# Microphone2.net
KiCad netlist of a schematic drawn in Altium Designer
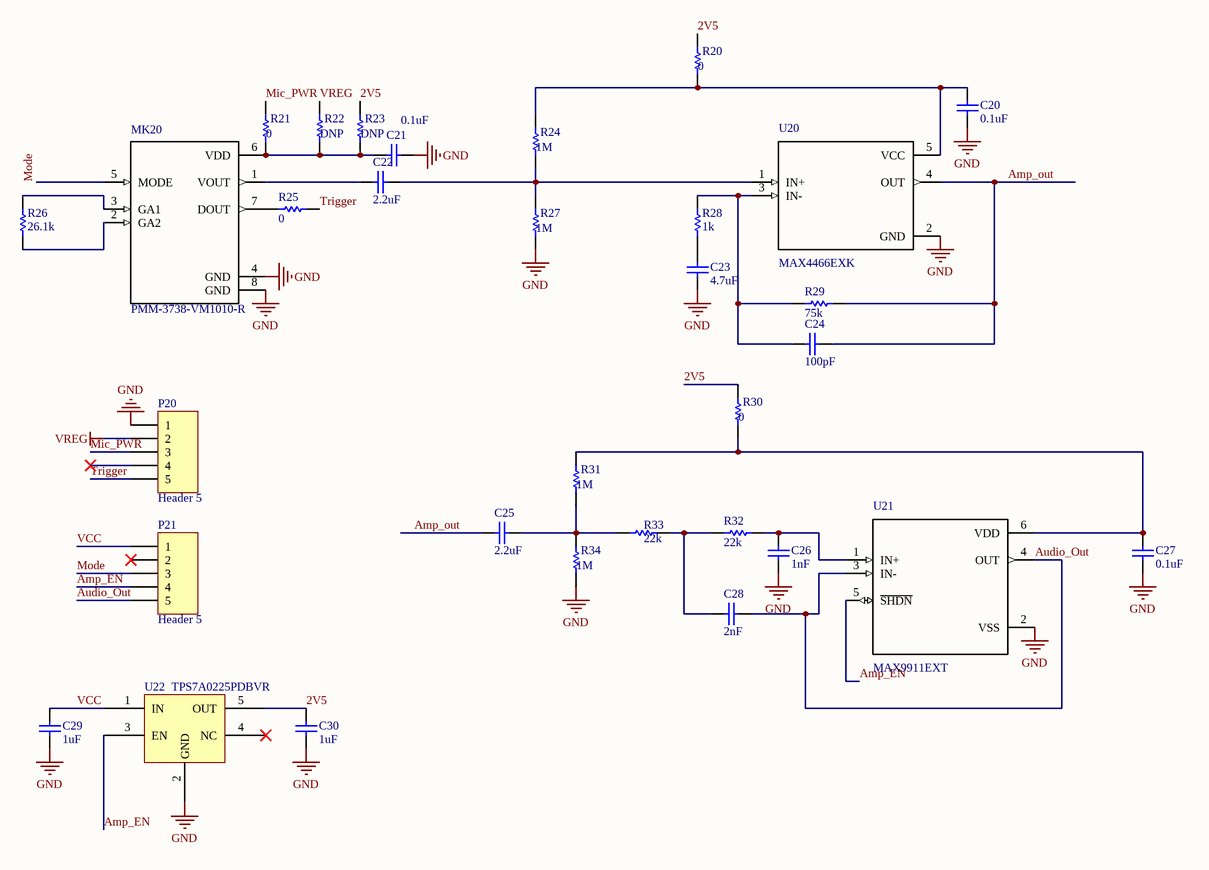
[diagram p0: Microphone2.SchDoc]

(export (version "E")
  (design (tool "Eeschema 10.0.6"))
  (components
    (comp (ref "C20")
      (value "0.1uF")
      (footprint "0402")
      (description "Ceramic Capacitor (Surface Mount)")
      (fields
        (field (name "DIGI-KEY PART NUMBER") "490-4759-1-ND")
        (field (name "MANUFACTURER") "Murata Electronics North America")
      )
      (libsource (lib "WISP_AD10") (part "Cap"))
    )
    (comp (ref "C21")
      (value "0.1uF")
      (footprint "0402")
      (description "Ceramic Capacitor (Surface Mount)")
      (fields
        (field (name "DIGI-KEY PART NUMBER") "490-4759-1-ND")
        (field (name "MANUFACTURER") "Murata Electronics North America")
      )
      (libsource (lib "WISP_AD10") (part "Cap"))
    )
    (comp (ref "C22")
      (value "2.2uF")
      (footprint "0402")
      (description "Ceramic Capacitor (Surface Mount)")
      (fields (field (name "DIGI-KEY PART NUMBER") "311-0.0JRCT-ND") (field (name "MANUFACTURER") "Yageo"))
      (libsource (lib "WISP_AD10") (part "Cap"))
    )
    (comp (ref "C23")
      (value "4.7uF")
      (footprint "0402")
      (description "Ceramic Capacitor (Surface Mount)")
      (fields
        (field (name "DIGI-KEY PART NUMBER") "490-14306-1-ND")
        (field (name "MANUFACTURER") "Murata Electronics")
      )
      (libsource (lib "WISP_AD10") (part "Cap"))
    )
    (comp (ref "C24")
      (value "100pF")
      (footprint "0402")
      (description "Ceramic Capacitor (Surface Mount)")
      (fields (field (name "DIGI-KEY PART NUMBER") "311-1024-1-ND") (field (name "MANUFACTURER") "Yageo"))
      (libsource (lib "WISP_AD10") (part "Cap"))
    )
    (comp (ref "C25")
      (value "2.2uF")
      (footprint "0402")
      (description "Ceramic Capacitor (Surface Mount)")
      (fields (field (name "DIGI-KEY PART NUMBER") "311-0.0JRCT-ND") (field (name "MANUFACTURER") "Yageo"))
      (libsource (lib "WISP_AD10") (part "Cap"))
    )
    (comp (ref "C26")
      (value "1nF")
      (footprint "0402")
      (description "Ceramic Capacitor (Surface Mount)")
      (fields
        (field (name "DIGI-KEY PART NUMBER") "490-4761-1-ND")
        (field (name "MANUFACTURER") "Murata Electronics")
      )
      (libsource (lib "WISP_AD10") (part "Cap"))
    )
    (comp (ref "C27")
      (value "0.1uF")
      (footprint "0402")
      (description "Ceramic Capacitor (Surface Mount)")
      (fields
        (field (name "DIGI-KEY PART NUMBER") "490-4759-1-ND")
        (field (name "MANUFACTURER") "Murata Electronics North America")
      )
      (libsource (lib "WISP_AD10") (part "Cap"))
    )
    (comp (ref "C28")
      (value "2nF")
      (footprint "0402")
      (description "Ceramic Capacitor (Surface Mount)")
      (fields
        (field (name "DIGI-KEY PART NUMBER") "478-10122-1-ND")
        (field (name "MANUFACTURER") "AVX Corporation")
      )
      (libsource (lib "WISP_AD10") (part "Cap"))
    )
    (comp (ref "C29")
      (value "1uF")
      (footprint "0402")
      (description "Ceramic Capacitor (Surface Mount)")
      (fields (field (name "DIGI-KEY PART NUMBER") "311-0.0JRCT-ND") (field (name "MANUFACTURER") "Yageo"))
      (libsource (lib "WISP_AD10") (part "Cap"))
    )
    (comp (ref "C30")
      (value "1uF")
      (footprint "0402")
      (description "Ceramic Capacitor (Surface Mount)")
      (fields (field (name "DIGI-KEY PART NUMBER") "311-0.0JRCT-ND") (field (name "MANUFACTURER") "Yageo"))
      (libsource (lib "WISP_AD10") (part "Cap"))
    )
    (comp (ref "MK20")
      (value "PMM-3738-VM1010-R")
      (footprint "MIC_PMM-3738-VM1010-R")
      (description "MEMS Microphone Omni-Directional 700 Ohm -38dBV 1.8V Rectangular Solder Pad T/R")
      (fields
        (field (name "MANUFACTURER PART NUMBER") "VM1010")
        (field (name "MANUFACTURER") "Vesper Technologies Inc.")
      )
      (libsource (lib "BLE") (part "PMM-3738-VM1010-R"))
    )
    (comp (ref "P20")
      (value "Header 5")
      (footprint "HDR1X5")
      (description "Header, 5-Pin")
      (fields (field (name "PUBLISHER") "Altium Limited"))
      (libsource (lib "Miscellaneous Connectors") (part "Header 5"))
    )
    (comp (ref "P21")
      (value "Header 5")
      (footprint "HDR1X5")
      (description "Header, 5-Pin")
      (fields (field (name "PUBLISHER") "Altium Limited"))
      (libsource (lib "Miscellaneous Connectors") (part "Header 5"))
    )
    (comp (ref "R20")
      (value "0")
      (footprint "0402")
      (description "Chip Resistor (Surface Mount)")
      (fields
        (field (name "MANUFACTURER") "Yageo")
        (field (name "MANUFACTURER PART NUMBER") "RC0402FR-071ML")
      )
      (libsource (lib "WISP_AD10") (part "Res"))
    )
    (comp (ref "R21")
      (value "0")
      (footprint "0402")
      (description "Chip Resistor (Surface Mount)")
      (fields
        (field (name "MANUFACTURER") "Yageo")
        (field (name "MANUFACTURER PART NUMBER") "RC0402FR-071ML")
      )
      (libsource (lib "WISP_AD10") (part "Res"))
    )
    (comp (ref "R22")
      (value "DNP")
      (footprint "0402")
      (description "Chip Resistor (Surface Mount)")
      (fields
        (field (name "MANUFACTURER") "Yageo")
        (field (name "MANUFACTURER PART NUMBER") "RC0402FR-071ML")
      )
      (libsource (lib "WISP_AD10") (part "Res"))
    )
    (comp (ref "R23")
      (value "DNP")
      (footprint "0402")
      (description "Chip Resistor (Surface Mount)")
      (fields
        (field (name "MANUFACTURER") "Yageo")
        (field (name "MANUFACTURER PART NUMBER") "RC0402FR-071ML")
      )
      (libsource (lib "WISP_AD10") (part "Res"))
    )
    (comp (ref "R24")
      (value "1M")
      (footprint "0402")
      (description "Chip Resistor (Surface Mount)")
      (fields
        (field (name "MANUFACTURER") "Yageo")
        (field (name "MANUFACTURER PART NUMBER") "RC0402FR-071ML")
      )
      (libsource (lib "WISP_AD10") (part "Res"))
    )
    (comp (ref "R25")
      (value "0")
      (footprint "0402")
      (description "Chip Resistor (Surface Mount)")
      (fields
        (field (name "MANUFACTURER") "Yageo")
        (field (name "MANUFACTURER PART NUMBER") "RC0402JR-070RL")
      )
      (libsource (lib "WISP_AD10") (part "Res"))
    )
    (comp (ref "R26")
      (value "26.1k")
      (footprint "0402")
      (description "Chip Resistor (Surface Mount)")
      (fields
        (field (name "MANUFACTURER") "Yageo")
        (field (name "MANUFACTURER PART NUMBER") "RC0402FR-0726K1L")
      )
      (libsource (lib "WISP_AD10") (part "Res"))
    )
    (comp (ref "R27")
      (value "1M")
      (footprint "0402")
      (description "Chip Resistor (Surface Mount)")
      (fields
        (field (name "MANUFACTURER") "Yageo")
        (field (name "MANUFACTURER PART NUMBER") "RC0402FR-071ML")
      )
      (libsource (lib "WISP_AD10") (part "Res"))
    )
    (comp (ref "R28")
      (value "1k")
      (footprint "0402")
      (description "Chip Resistor (Surface Mount)")
      (fields
        (field (name "MANUFACTURER") "Yageo")
        (field (name "MANUFACTURER PART NUMBER") "RC0402FR-071KL")
      )
      (libsource (lib "WISP_AD10") (part "Res"))
    )
    (comp (ref "R29")
      (value "75k")
      (footprint "0402")
      (description "Chip Resistor (Surface Mount)")
      (fields
        (field (name "MANUFACTURER") "Yageo")
        (field (name "MANUFACTURER PART NUMBER") "RC0402FR-0775KL")
      )
      (libsource (lib "WISP_AD10") (part "Res"))
    )
    (comp (ref "R30")
      (value "0")
      (footprint "0402")
      (description "Chip Resistor (Surface Mount)")
      (fields
        (field (name "MANUFACTURER") "Yageo")
        (field (name "MANUFACTURER PART NUMBER") "RC0402FR-071ML")
      )
      (libsource (lib "WISP_AD10") (part "Res"))
    )
    (comp (ref "R31")
      (value "1M")
      (footprint "0402")
      (description "Chip Resistor (Surface Mount)")
      (fields
        (field (name "MANUFACTURER") "Yageo")
        (field (name "MANUFACTURER PART NUMBER") "RC0402FR-071ML")
      )
      (libsource (lib "WISP_AD10") (part "Res"))
    )
    (comp (ref "R32")
      (value "22k")
      (footprint "0402")
      (description "Chip Resistor (Surface Mount)")
      (fields
        (field (name "MANUFACTURER") "Yageo")
        (field (name "MANUFACTURER PART NUMBER") "RT0402BRD0722KL")
      )
      (libsource (lib "WISP_AD10") (part "Res"))
    )
    (comp (ref "R33")
      (value "22k")
      (footprint "0402")
      (description "Chip Resistor (Surface Mount)")
      (fields
        (field (name "MANUFACTURER") "Yageo")
        (field (name "MANUFACTURER PART NUMBER") "RT0402BRD0722KL")
      )
      (libsource (lib "WISP_AD10") (part "Res"))
    )
    (comp (ref "R34")
      (value "1M")
      (footprint "0402")
      (description "Chip Resistor (Surface Mount)")
      (fields
        (field (name "MANUFACTURER") "Yageo")
        (field (name "MANUFACTURER PART NUMBER") "RC0402FR-071ML")
      )
      (libsource (lib "WISP_AD10") (part "Res"))
    )
    (comp (ref "U20")
      (value "MAX4466EXK")
      (footprint "SOT65P210X110-5N")
      (description "Audio Amp Microphone 1-CH Mono Class-AB 5-Pin SC70")
      (fields
        (field (name "MANUFACTURER") "Maxim Integrated")
        (field (name "MANUFACTURER PART NUMBER") "MAX4466EXK+T")
      )
      (libsource (lib "BLE") (part "MAX4466EXK"))
    )
    (comp (ref "U21")
      (value "MAX9911EXT")
      (footprint "MAX9911EXT")
      (description "Operational amplifier; 1.8Ã·5.5VDC; Channels: 1; SC70-6")
      (fields (field (name "MANUFACTURER PART NUMBER") "MAX9911EXT+T") (field (name "MANUFACTURER") "Maxim"))
      (libsource (lib "BLE") (part "MAX9911EXT"))
    )
    (comp (ref "U22")
      (value "TPS7A0225PDBVR")
      (footprint "SOT23-5")
      (description "IC REG LINEAR 2.5V 200MA SOT23-5")
      (libsource (lib "WISP_AD10") (part "TPS7A0218PDBVR"))
    )
  )
  (nets
    (net (code "1") (name "/2V5") (class "Default")
      (node (ref "C30") (pin "2") (pinfunction "2_2") (pintype "passive"))
      (node (ref "R20") (pin "1") (pinfunction "1_1") (pintype "passive"))
      (node (ref "R23") (pin "1") (pinfunction "1_1") (pintype "passive"))
      (node (ref "R30") (pin "1") (pinfunction "1_1") (pintype "passive"))
      (node (ref "U22") (pin "5") (pinfunction "OUT_5") (pintype "passive"))
    )
    (net (code "2") (name "/Amp_EN") (class "Default")
      (node (ref "P21") (pin "4") (pinfunction "4_4") (pintype "passive"))
      (node (ref "U21") (pin "5") (pinfunction "~{SHDN}_5") (pintype "bidirectional"))
      (node (ref "U22") (pin "3") (pinfunction "EN_3") (pintype "passive"))
    )
    (net (code "3") (name "/Amp_out") (class "Default")
      (node (ref "C24") (pin "1") (pinfunction "1_1") (pintype "passive"))
      (node (ref "C25") (pin "1") (pinfunction "1_1") (pintype "passive"))
      (node (ref "R29") (pin "2") (pinfunction "2_2") (pintype "passive"))
      (node (ref "U20") (pin "4") (pinfunction "OUT_4") (pintype "output"))
    )
    (net (code "4") (name "/Audio_Out") (class "Default")
      (node (ref "C28") (pin "1") (pinfunction "1_1") (pintype "passive"))
      (node (ref "P21") (pin "5") (pinfunction "5_5") (pintype "passive"))
      (node (ref "U21") (pin "3") (pinfunction "IN-_3") (pintype "input"))
      (node (ref "U21") (pin "4") (pinfunction "OUT_4") (pintype "output"))
    )
    (net (code "5") (name "/Mic_PWR") (class "Default")
      (node (ref "P20") (pin "3") (pinfunction "3_3") (pintype "passive"))
      (node (ref "R21") (pin "1") (pinfunction "1_1") (pintype "passive"))
    )
    (net (code "6") (name "/Mode") (class "Default")
      (node (ref "MK20") (pin "5") (pinfunction "MODE_5") (pintype "input"))
      (node (ref "P21") (pin "3") (pinfunction "3_3") (pintype "passive"))
    )
    (net (code "7") (name "/Trigger") (class "Default")
      (node (ref "P20") (pin "5") (pinfunction "5_5") (pintype "passive"))
      (node (ref "R25") (pin "2") (pinfunction "2_2") (pintype "passive"))
    )
    (net (code "8") (name "/VCC") (class "Default")
      (node (ref "C29") (pin "2") (pinfunction "2_2") (pintype "passive"))
      (node (ref "P21") (pin "1") (pinfunction "1_1") (pintype "passive"))
      (node (ref "U22") (pin "1") (pinfunction "IN_1") (pintype "passive"))
    )
    (net (code "9") (name "GND") (class "Default")
      (node (ref "C20") (pin "2") (pinfunction "2_2") (pintype "passive"))
      (node (ref "C21") (pin "2") (pinfunction "2_2") (pintype "passive"))
      (node (ref "C23") (pin "1") (pinfunction "1_1") (pintype "passive"))
      (node (ref "C26") (pin "2") (pinfunction "2_2") (pintype "passive"))
      (node (ref "C27") (pin "1") (pinfunction "1_1") (pintype "passive"))
      (node (ref "C29") (pin "1") (pinfunction "1_1") (pintype "passive"))
      (node (ref "C30") (pin "1") (pinfunction "1_1") (pintype "passive"))
      (node (ref "MK20") (pin "4") (pinfunction "GND_4") (pintype "power_in"))
      (node (ref "MK20") (pin "8") (pinfunction "GND_8") (pintype "power_in"))
      (node (ref "P20") (pin "1") (pinfunction "1_1") (pintype "passive"))
      (node (ref "R27") (pin "2") (pinfunction "2_2") (pintype "passive"))
      (node (ref "R34") (pin "1") (pinfunction "1_1") (pintype "passive"))
      (node (ref "U20") (pin "2") (pinfunction "GND_2") (pintype "power_in"))
      (node (ref "U21") (pin "2") (pinfunction "VSS_2") (pintype "power_in"))
      (node (ref "U22") (pin "2") (pinfunction "GND_2") (pintype "passive"))
    )
    (net (code "10") (name "Net-(C23-Pad2)") (class "Default")
      (node (ref "C23") (pin "2") (pinfunction "2_2") (pintype "passive"))
      (node (ref "R28") (pin "2") (pinfunction "2_2") (pintype "passive"))
    )
    (net (code "11") (name "Net-(C25-Pad2)") (class "Default")
      (node (ref "C25") (pin "2") (pinfunction "2_2") (pintype "passive"))
      (node (ref "R31") (pin "1") (pinfunction "1_1") (pintype "passive"))
      (node (ref "R33") (pin "1") (pinfunction "1_1") (pintype "passive"))
      (node (ref "R34") (pin "2") (pinfunction "2_2") (pintype "passive"))
    )
    (net (code "12") (name "Net-(C28-Pad2)") (class "Default")
      (node (ref "C28") (pin "2") (pinfunction "2_2") (pintype "passive"))
      (node (ref "R32") (pin "1") (pinfunction "1_1") (pintype "passive"))
      (node (ref "R33") (pin "2") (pinfunction "2_2") (pintype "passive"))
    )
    (net (code "13") (name "Net-(MK20-DOUT)") (class "Default")
      (node (ref "MK20") (pin "7") (pinfunction "DOUT_7") (pintype "output"))
      (node (ref "R25") (pin "1") (pinfunction "1_1") (pintype "passive"))
    )
    (net (code "14") (name "Net-(MK20-GA1)") (class "Default")
      (node (ref "MK20") (pin "3") (pinfunction "GA1_3") (pintype "input"))
      (node (ref "R26") (pin "1") (pinfunction "1_1") (pintype "passive"))
    )
    (net (code "15") (name "Net-(MK20-GA2)") (class "Default")
      (node (ref "MK20") (pin "2") (pinfunction "GA2_2") (pintype "input"))
      (node (ref "R26") (pin "2") (pinfunction "2_2") (pintype "passive"))
    )
    (net (code "16") (name "Net-(MK20-VDD)") (class "Default")
      (node (ref "C21") (pin "1") (pinfunction "1_1") (pintype "passive"))
      (node (ref "MK20") (pin "6") (pinfunction "VDD_6") (pintype "power_in"))
      (node (ref "R21") (pin "2") (pinfunction "2_2") (pintype "passive"))
      (node (ref "R22") (pin "2") (pinfunction "2_2") (pintype "passive"))
      (node (ref "R23") (pin "2") (pinfunction "2_2") (pintype "passive"))
    )
    (net (code "17") (name "Net-(MK20-VOUT)") (class "Default")
      (node (ref "C22") (pin "1") (pinfunction "1_1") (pintype "passive"))
      (node (ref "MK20") (pin "1") (pinfunction "VOUT_1") (pintype "output"))
    )
    (net (code "18") (name "Net-(U20-IN+)") (class "Default")
      (node (ref "C22") (pin "2") (pinfunction "2_2") (pintype "passive"))
      (node (ref "R24") (pin "2") (pinfunction "2_2") (pintype "passive"))
      (node (ref "R27") (pin "1") (pinfunction "1_1") (pintype "passive"))
      (node (ref "U20") (pin "1") (pinfunction "IN+_1") (pintype "input"))
    )
    (net (code "19") (name "Net-(U20-IN-)") (class "Default")
      (node (ref "C24") (pin "2") (pinfunction "2_2") (pintype "passive"))
      (node (ref "R28") (pin "1") (pinfunction "1_1") (pintype "passive"))
      (node (ref "R29") (pin "1") (pinfunction "1_1") (pintype "passive"))
      (node (ref "U20") (pin "3") (pinfunction "IN-_3") (pintype "input"))
    )
    (net (code "20") (name "Net-(U20-VCC)") (class "Default")
      (node (ref "C20") (pin "1") (pinfunction "1_1") (pintype "passive"))
      (node (ref "R20") (pin "2") (pinfunction "2_2") (pintype "passive"))
      (node (ref "R24") (pin "1") (pinfunction "1_1") (pintype "passive"))
      (node (ref "U20") (pin "5") (pinfunction "VCC_5") (pintype "power_in"))
    )
    (net (code "21") (name "Net-(U21-IN+)") (class "Default")
      (node (ref "C26") (pin "1") (pinfunction "1_1") (pintype "passive"))
      (node (ref "R32") (pin "2") (pinfunction "2_2") (pintype "passive"))
      (node (ref "U21") (pin "1") (pinfunction "IN+_1") (pintype "input"))
    )
    (net (code "22") (name "Net-(U21-VDD)") (class "Default")
      (node (ref "C27") (pin "2") (pinfunction "2_2") (pintype "passive"))
      (node (ref "R30") (pin "2") (pinfunction "2_2") (pintype "passive"))
      (node (ref "R31") (pin "2") (pinfunction "2_2") (pintype "passive"))
      (node (ref "U21") (pin "6") (pinfunction "VDD_6") (pintype "power_in"))
    )
    (net (code "23") (name "VREG") (class "Default")
      (node (ref "P20") (pin "2") (pinfunction "2_2") (pintype "passive"))
      (node (ref "R22") (pin "1") (pinfunction "1_1") (pintype "passive"))
    )
    (net (code "24") (name "unconnected-(P20-Pad4)") (class "Default")
      (node (ref "P20") (pin "4") (pinfunction "4_4") (pintype "passive+no_connect"))
    )
    (net (code "25") (name "unconnected-(P21-Pad2)") (class "Default")
      (node (ref "P21") (pin "2") (pinfunction "2_2") (pintype "passive+no_connect"))
    )
    (net (code "26") (name "unconnected-(U22-NC-Pad4)") (class "Default")
      (node (ref "U22") (pin "4") (pinfunction "NC_4") (pintype "passive+no_connect"))
    )
  )
)
